# Main.net
KiCad netlist of a schematic drawn in Altium Designer
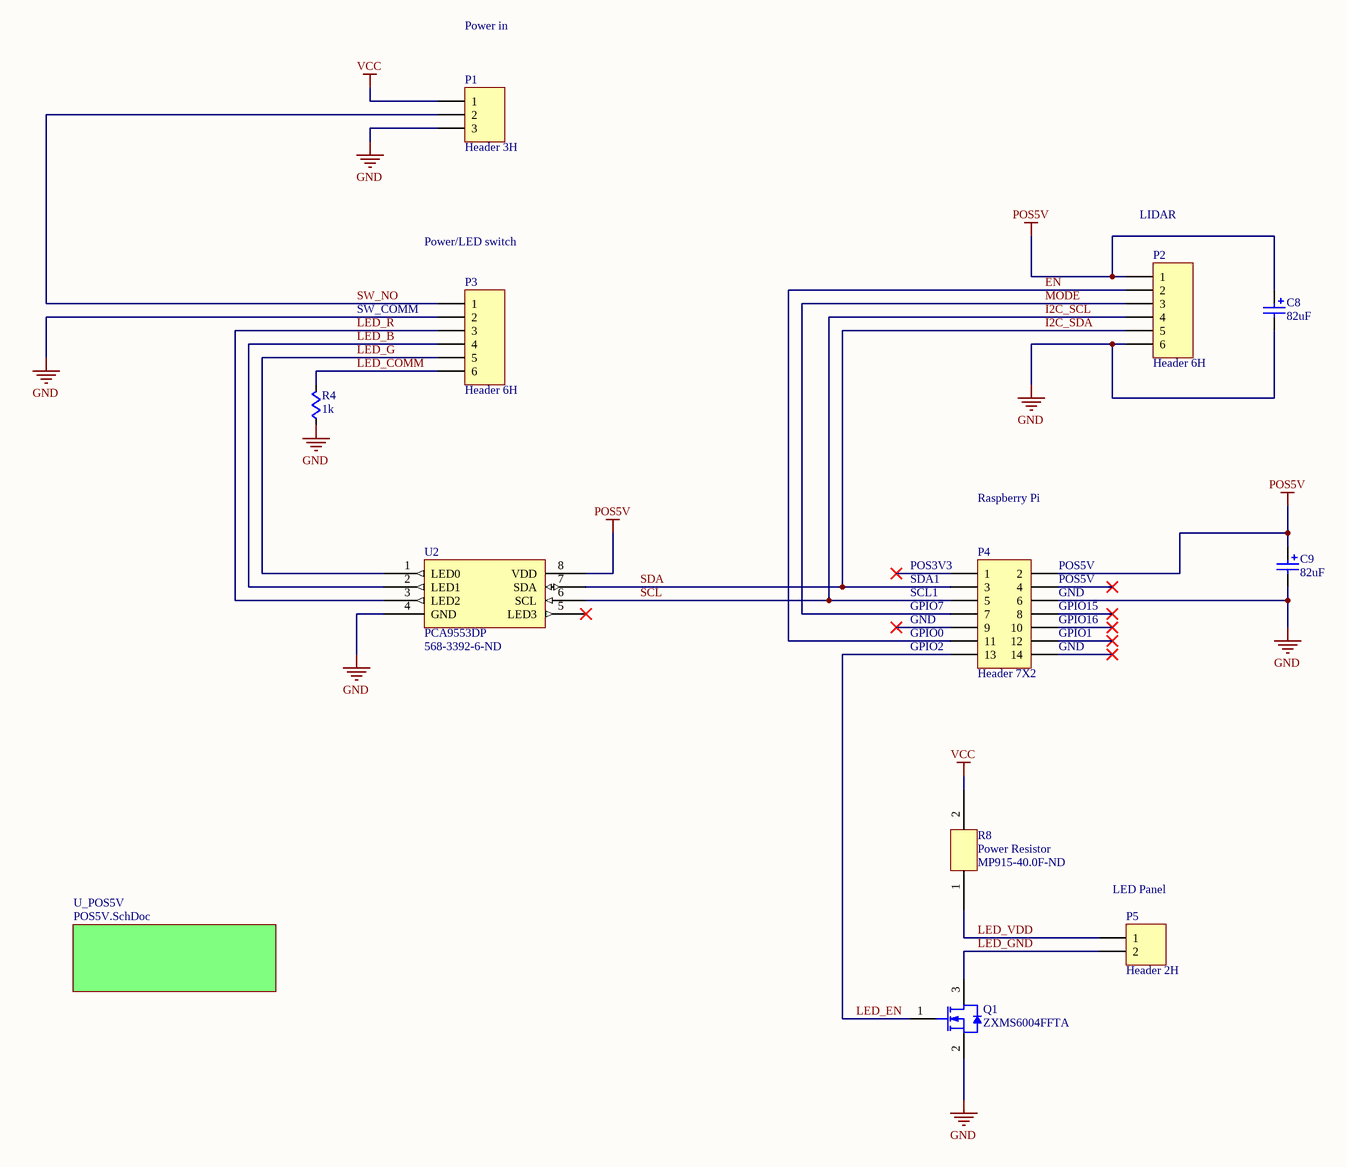
[diagram p0: Main.SchDoc]

(export (version "E")
  (design (tool "Eeschema 10.0.6"))
  (components
    (comp (ref "C8")
      (value "82uF")
      (footprint "CAP_EEFK_D8")
      (description "Polarized Capacitor (Surface Mount)")
      (fields (field (name "MANUFACTURER_PART_NUMBER") "EEEFK1V680XP"))
      (libsource (lib "AEVC-lib") (part "EEEFK1V680XP"))
    )
    (comp (ref "C9")
      (value "82uF")
      (footprint "CAP_EEFK_D8")
      (description "Polarized Capacitor (Surface Mount)")
      (fields (field (name "MANUFACTURER_PART_NUMBER") "EEEFK1V680XP"))
      (libsource (lib "AEVC-lib") (part "EEEFK1V680XP"))
    )
    (comp (ref "P1")
      (value "Header 3H")
      (footprint "HDR1X3H")
      (description "Header, 3-Pin, Right Angle")
      (fields (field (name "PUBLISHER") "Altium Limited"))
      (libsource (lib "Miscellaneous Connectors") (part "Header 3H"))
    )
    (comp (ref "P2")
      (value "Header 6H")
      (footprint "HDR1X6H")
      (description "Header, 6-Pin, Right Angle")
      (fields (field (name "PUBLISHER") "Altium Limited"))
      (libsource (lib "Miscellaneous Connectors") (part "Header 6H"))
    )
    (comp (ref "P3")
      (value "Header 6H")
      (footprint "HDR1X6H")
      (description "Header, 6-Pin, Right Angle")
      (fields (field (name "PUBLISHER") "Altium Limited"))
      (libsource (lib "Miscellaneous Connectors") (part "Header 6H"))
    )
    (comp (ref "P4")
      (value "Header 7X2")
      (footprint "HDR2X7")
      (description "Header, 7-Pin, Dual row")
      (fields (field (name "PUBLISHER") "Altium Limited"))
      (libsource (lib "Miscellaneous Connectors") (part "Header 7X2"))
    )
    (comp (ref "P5")
      (value "Header 2H")
      (footprint "HDR1X2H")
      (description "Header, 2-Pin, Right Angle")
      (fields (field (name "PUBLISHER") "Altium Limited"))
      (libsource (lib "Miscellaneous Connectors") (part "Header 2H"))
    )
    (comp (ref "Q1")
      (value "ZXMS6004FFTA")
      (footprint "DIOD-SOT23F-3_V")
      (fields (field (name "MANUFACTURER") "Diodes Inc"))
      (libsource (lib "Altium Content Vault") (part "NEMOS-GSD-3"))
    )
    (comp (ref "R4")
      (value "1k")
      (footprint "R0805")
      (description "resistor")
      (fields (field (name "Comment") "Res"))
      (libsource (lib "ChipComponents") (part "Res"))
    )
    (comp (ref "R8")
      (value "Power Resistor")
      (footprint "MP915")
      (fields (field (name "SUPPLIER PART NUMBER 1") "MP915-40.0F-ND"))
      (libsource (lib "AEVC-lib") (part "MP915-40.0-1%"))
    )
    (comp (ref "U2")
      (value "PCA9553DP")
      (footprint "TSSOP8")
      (description "LED Driver, I2C")
      (fields (field (name "SUPPLIER PART NUMBER 1") "568-3392-6-ND"))
      (libsource (lib "AEVC-lib") (part "PCA9553DP"))
    )
  )
  (nets
    (net (code "1") (name "/EN") (class "Default")
      (node (ref "P2") (pin "2") (pinfunction "2_2") (pintype "passive"))
      (node (ref "P4") (pin "11") (pinfunction "11_11") (pintype "passive"))
    )
    (net (code "2") (name "/I2C_SCL") (class "Default")
      (node (ref "P2") (pin "4") (pinfunction "4_4") (pintype "passive"))
      (node (ref "P4") (pin "5") (pinfunction "5_5") (pintype "passive"))
      (node (ref "U2") (pin "6") (pinfunction "SCL_6") (pintype "input"))
    )
    (net (code "3") (name "/I2C_SDA") (class "Default")
      (node (ref "P2") (pin "5") (pinfunction "5_5") (pintype "passive"))
      (node (ref "P4") (pin "3") (pinfunction "3_3") (pintype "passive"))
      (node (ref "U2") (pin "7") (pinfunction "SDA_7") (pintype "bidirectional"))
    )
    (net (code "4") (name "/LED_B") (class "Default")
      (node (ref "P3") (pin "4") (pinfunction "4_4") (pintype "passive"))
      (node (ref "U2") (pin "2") (pinfunction "LED1_2") (pintype "output"))
    )
    (net (code "5") (name "/LED_COMM") (class "Default")
      (node (ref "P3") (pin "6") (pinfunction "6_6") (pintype "passive"))
      (node (ref "R4") (pin "2") (pinfunction "2_2") (pintype "passive"))
    )
    (net (code "6") (name "/LED_EN") (class "Default")
      (node (ref "P4") (pin "13") (pinfunction "13_13") (pintype "passive"))
      (node (ref "Q1") (pin "1") (pinfunction "G_1") (pintype "passive"))
    )
    (net (code "7") (name "/LED_G") (class "Default")
      (node (ref "P3") (pin "5") (pinfunction "5_5") (pintype "passive"))
      (node (ref "U2") (pin "1") (pinfunction "LED0_1") (pintype "output"))
    )
    (net (code "8") (name "/LED_GND") (class "Default")
      (node (ref "P5") (pin "2") (pinfunction "2_2") (pintype "passive"))
      (node (ref "Q1") (pin "3") (pinfunction "D_3") (pintype "passive"))
    )
    (net (code "9") (name "/LED_R") (class "Default")
      (node (ref "P3") (pin "3") (pinfunction "3_3") (pintype "passive"))
      (node (ref "U2") (pin "3") (pinfunction "LED2_3") (pintype "output"))
    )
    (net (code "10") (name "/LED_VDD") (class "Default")
      (node (ref "P5") (pin "1") (pinfunction "1_1") (pintype "passive"))
      (node (ref "R8") (pin "1") (pintype "power_in"))
    )
    (net (code "11") (name "/MODE") (class "Default")
      (node (ref "P2") (pin "3") (pinfunction "3_3") (pintype "passive"))
      (node (ref "P4") (pin "7") (pinfunction "7_7") (pintype "passive"))
    )
    (net (code "12") (name "/SW_NO") (class "Default")
      (node (ref "P1") (pin "2") (pinfunction "2_2") (pintype "passive"))
      (node (ref "P3") (pin "1") (pinfunction "1_1") (pintype "passive"))
    )
    (net (code "13") (name "GND") (class "Default")
      (node (ref "C8") (pin "2") (pinfunction "2_2") (pintype "passive"))
      (node (ref "C9") (pin "2") (pinfunction "2_2") (pintype "passive"))
      (node (ref "P1") (pin "3") (pinfunction "3_3") (pintype "passive"))
      (node (ref "P2") (pin "6") (pinfunction "6_6") (pintype "passive"))
      (node (ref "P3") (pin "2") (pinfunction "2_2") (pintype "passive"))
      (node (ref "P4") (pin "6") (pinfunction "6_6") (pintype "passive"))
      (node (ref "Q1") (pin "2") (pinfunction "S_2") (pintype "passive"))
      (node (ref "R4") (pin "1") (pinfunction "1_1") (pintype "passive"))
      (node (ref "U2") (pin "4") (pinfunction "GND_4") (pintype "power_in"))
    )
    (net (code "14") (name "POS5V") (class "Default")
      (node (ref "C8") (pin "1") (pinfunction "1_1") (pintype "passive"))
      (node (ref "C9") (pin "1") (pinfunction "1_1") (pintype "passive"))
      (node (ref "P2") (pin "1") (pinfunction "1_1") (pintype "passive"))
      (node (ref "P4") (pin "2") (pinfunction "2_2") (pintype "passive"))
      (node (ref "U2") (pin "8") (pinfunction "VDD_8") (pintype "power_in"))
    )
    (net (code "15") (name "VCC") (class "Default")
      (node (ref "P1") (pin "1") (pinfunction "1_1") (pintype "passive"))
      (node (ref "R8") (pin "2") (pintype "power_in"))
    )
    (net (code "16") (name "unconnected-(P4-Pad1)") (class "Default")
      (node (ref "P4") (pin "1") (pinfunction "1_1") (pintype "passive+no_connect"))
    )
    (net (code "17") (name "unconnected-(P4-Pad4)") (class "Default")
      (node (ref "P4") (pin "4") (pinfunction "4_4") (pintype "passive+no_connect"))
    )
    (net (code "18") (name "unconnected-(P4-Pad8)") (class "Default")
      (node (ref "P4") (pin "8") (pinfunction "8_8") (pintype "passive+no_connect"))
    )
    (net (code "19") (name "unconnected-(P4-Pad9)") (class "Default")
      (node (ref "P4") (pin "9") (pinfunction "9_9") (pintype "passive+no_connect"))
    )
    (net (code "20") (name "unconnected-(P4-Pad10)") (class "Default")
      (node (ref "P4") (pin "10") (pinfunction "10_10") (pintype "passive+no_connect"))
    )
    (net (code "21") (name "unconnected-(P4-Pad12)") (class "Default")
      (node (ref "P4") (pin "12") (pinfunction "12_12") (pintype "passive+no_connect"))
    )
    (net (code "22") (name "unconnected-(P4-Pad14)") (class "Default")
      (node (ref "P4") (pin "14") (pinfunction "14_14") (pintype "passive+no_connect"))
    )
    (net (code "23") (name "unconnected-(U2-LED3-Pad5)") (class "Default")
      (node (ref "U2") (pin "5") (pinfunction "LED3_5") (pintype "output+no_connect"))
    )
  )
)
